# LM317.net
KiCad netlist of a schematic drawn in Altium Designer
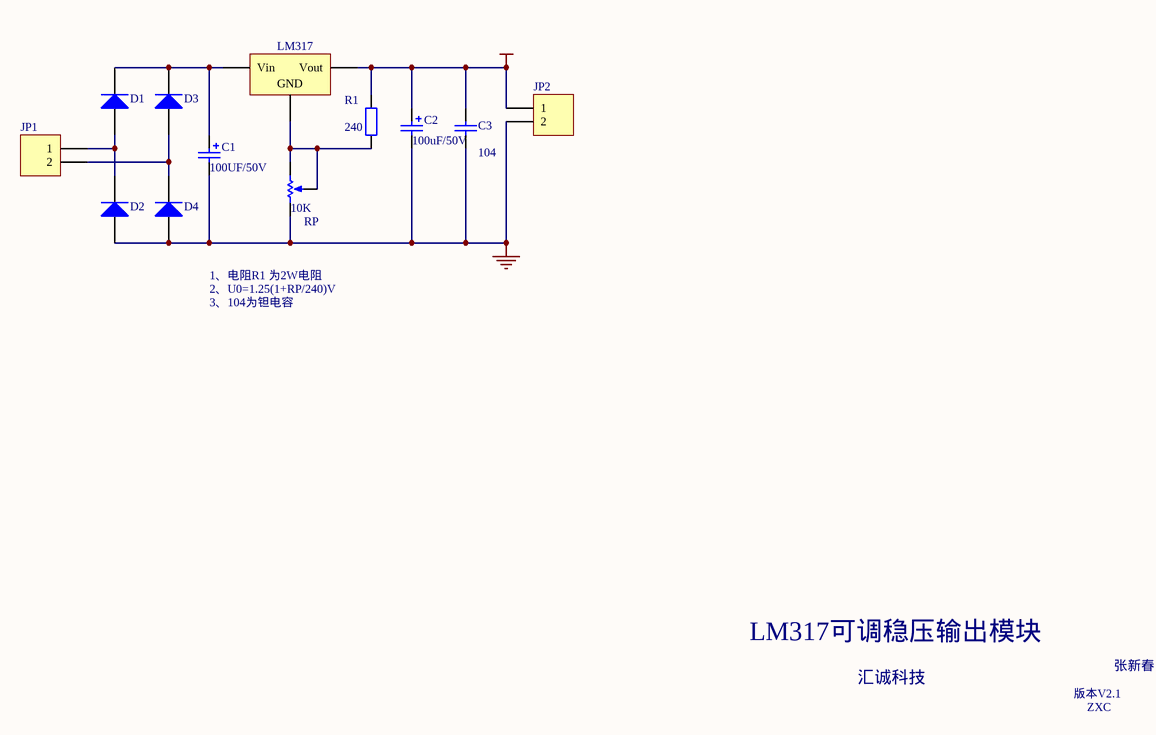
[diagram p0: LM317可调稳压输出模块.SchDoc]

(export (version "E")
  (design (tool "Eeschema 10.0.6"))
  (components
    (comp (ref "C1")
      (value "100UF/50V")
      (footprint "C-DJ-6")
      (description "电解电容")
      (fields (field (name "Comment") "DJDR") (field (name "PUBLISHER") "Altium Limited"))
      (libsource (lib "zxcourhc") (part "DJDR"))
    )
    (comp (ref "C2")
      (value "100uF/50V")
      (footprint "C-DJ-6")
      (description "电解电容")
      (fields (field (name "Comment") "DJDR") (field (name "PUBLISHER") "Altium Limited"))
      (libsource (lib "zxcourhc") (part "DJDR"))
    )
    (comp (ref "C3")
      (value "104")
      (footprint "CPDR")
      (description "瓷片电容")
      (fields (field (name "Comment") "CPDR") (field (name "PUBLISHER") "Altium Limited"))
      (libsource (lib "zxcourhc") (part "CPDR"))
    )
    (comp (ref "D1")
      (value "Diode 1N4007")
      (footprint "zxcourhc:D-ZL-10")
      (description "1 Amp General Purpose Rectifier")
      (fields (field (name "PUBLISHER") "Altium Limited"))
      (libsource (lib "Miscellaneous Devices") (part "Diode 1N4007"))
    )
    (comp (ref "D2")
      (value "Diode 1N4007")
      (footprint "zxcourhc:D-ZL-10")
      (description "1 Amp General Purpose Rectifier")
      (fields (field (name "PUBLISHER") "Altium Limited"))
      (libsource (lib "Miscellaneous Devices") (part "Diode 1N4007"))
    )
    (comp (ref "D3")
      (value "Diode 1N4007")
      (footprint "zxcourhc:D-ZL-10")
      (description "1 Amp General Purpose Rectifier")
      (fields (field (name "PUBLISHER") "Altium Limited"))
      (libsource (lib "Miscellaneous Devices") (part "Diode 1N4007"))
    )
    (comp (ref "D4")
      (value "Diode 1N4007")
      (footprint "zxcourhc:D-ZL-10")
      (description "1 Amp General Purpose Rectifier")
      (fields (field (name "PUBLISHER") "Altium Limited"))
      (libsource (lib "Miscellaneous Devices") (part "Diode 1N4007"))
    )
    (comp (ref "JP1")
      (value "PZ_2")
      (footprint "zxcourhc:JIKEKE")
      (description "排针——2")
      (fields (field (name "PUBLISHER") "Altium Limited"))
      (libsource (lib "") (part "PZ_2_1"))
    )
    (comp (ref "JP2")
      (value "PZ_2")
      (footprint "JIKEKE")
      (description "排针——2")
      (fields (field (name "PUBLISHER") "Altium Limited"))
      (libsource (lib "zxcourhc") (part "PZ_2"))
    )
    (comp (ref "LM317")
      (value "SDWYG")
      (footprint "wyk")
      (description "三端稳压器")
      (fields (field (name "PUBLISHER") "Altium Limited"))
      (libsource (lib "zxcourhc") (part "SDWYG"))
    )
    (comp (ref "R1")
      (value "240")
      (footprint "ZCDZL")
      (description "电阻")
      (fields (field (name "Comment") "Res") (field (name "PUBLISHER") "Altium Limited"))
      (libsource (lib "zxcourhc") (part "Res"))
    )
    (comp (ref "RP")
      (value "10K")
      (footprint "SIP3-D")
      (description "Potentiometer")
      (fields (field (name "Comment") "RPot") (field (name "PUBLISHER") "Altium Limited"))
      (libsource (lib "Miscellaneous Devices") (part "RPot"))
    )
  )
  (nets
    (net (code "1") (name "GND") (class "Default")
      (node (ref "C1") (pin "2") (pinfunction "2_2") (pintype "passive"))
      (node (ref "C2") (pin "2") (pinfunction "2_2") (pintype "passive"))
      (node (ref "C3") (pin "1") (pinfunction "1_1") (pintype "passive"))
      (node (ref "D2") (pin "1") (pinfunction "A_1") (pintype "passive"))
      (node (ref "D4") (pin "1") (pinfunction "A_1") (pintype "passive"))
      (node (ref "JP2") (pin "2") (pinfunction "2_2") (pintype "passive"))
      (node (ref "RP") (pin "1") (pinfunction "TOP_1") (pintype "passive"))
    )
    (net (code "2") (name "Net-(D1-A)") (class "Default")
      (node (ref "D1") (pin "1") (pinfunction "A_1") (pintype "passive"))
      (node (ref "D2") (pin "2") (pinfunction "K_2") (pintype "passive"))
      (node (ref "JP1") (pin "1") (pinfunction "1_1") (pintype "passive"))
    )
    (net (code "3") (name "Net-(D1-K)") (class "Default")
      (node (ref "C1") (pin "1") (pinfunction "1_1") (pintype "passive"))
      (node (ref "D1") (pin "2") (pinfunction "K_2") (pintype "passive"))
      (node (ref "D3") (pin "2") (pinfunction "K_2") (pintype "passive"))
      (node (ref "LM317") (pin "3") (pinfunction "Vin_3") (pintype "passive"))
    )
    (net (code "4") (name "Net-(D3-A)") (class "Default")
      (node (ref "D3") (pin "1") (pinfunction "A_1") (pintype "passive"))
      (node (ref "D4") (pin "2") (pinfunction "K_2") (pintype "passive"))
      (node (ref "JP1") (pin "2") (pinfunction "2_2") (pintype "passive"))
    )
    (net (code "5") (name "Net-(LM317-AD)") (class "Default")
      (node (ref "LM317") (pin "1") (pinfunction "AD_1") (pintype "passive"))
      (node (ref "R1") (pin "1") (pinfunction "1_1") (pintype "passive"))
      (node (ref "RP") (pin "2") (pinfunction "BOT_2") (pintype "passive"))
      (node (ref "RP") (pin "3") (pinfunction "TAP_3") (pintype "passive"))
    )
    (net (code "6") (name "VCC") (class "Default")
      (node (ref "C2") (pin "1") (pinfunction "1_1") (pintype "passive"))
      (node (ref "C3") (pin "2") (pinfunction "2_2") (pintype "passive"))
      (node (ref "JP2") (pin "1") (pinfunction "1_1") (pintype "passive"))
      (node (ref "LM317") (pin "2") (pinfunction "Vout_2") (pintype "passive"))
      (node (ref "R1") (pin "2") (pinfunction "2_2") (pintype "passive"))
    )
  )
)
